# Main.net
KiCad netlist of a schematic drawn in Altium Designer
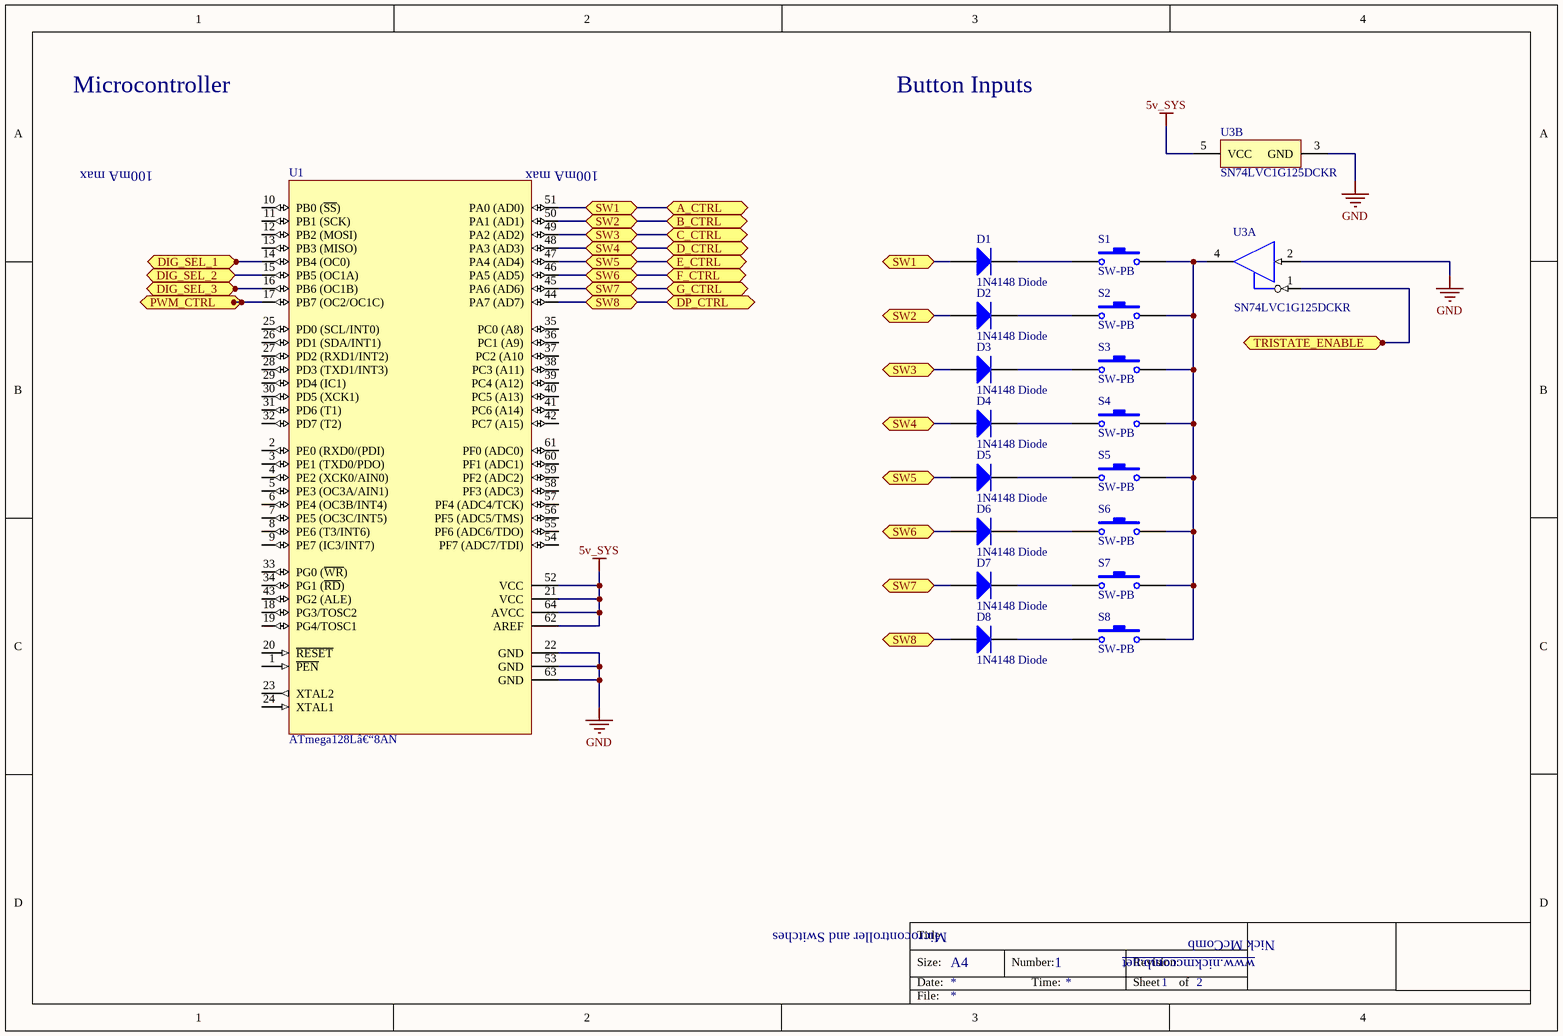
[diagram p0: Main.SchDoc]

(export (version "E")
  (design (tool "Eeschema 10.0.6"))
  (components
    (comp (ref "D1")
      (value "1N4148 Diode")
      (footprint "S01575 Diode")
      (description "Diode")
      (libsource (lib "lab2") (part "Diode"))
    )
    (comp (ref "D2")
      (value "1N4148 Diode")
      (footprint "S01575 Diode")
      (description "Diode")
      (libsource (lib "lab2") (part "Diode"))
    )
    (comp (ref "D3")
      (value "1N4148 Diode")
      (footprint "S01575 Diode")
      (description "Diode")
      (libsource (lib "lab2") (part "Diode"))
    )
    (comp (ref "D4")
      (value "1N4148 Diode")
      (footprint "S01575 Diode")
      (description "Diode")
      (libsource (lib "lab2") (part "Diode"))
    )
    (comp (ref "D5")
      (value "1N4148 Diode")
      (footprint "S01575 Diode")
      (description "Diode")
      (libsource (lib "lab2") (part "Diode"))
    )
    (comp (ref "D6")
      (value "1N4148 Diode")
      (footprint "S01575 Diode")
      (description "Diode")
      (libsource (lib "lab2") (part "Diode"))
    )
    (comp (ref "D7")
      (value "1N4148 Diode")
      (footprint "S01575 Diode")
      (description "Diode")
      (libsource (lib "lab2") (part "Diode"))
    )
    (comp (ref "D8")
      (value "1N4148 Diode")
      (footprint "S01575 Diode")
      (description "Diode")
      (libsource (lib "lab2") (part "Diode"))
    )
    (comp (ref "S1")
      (value "SW-PB")
      (footprint "SW-PB")
      (description "Switch")
      (libsource (lib "lab2") (part "SW-PB"))
    )
    (comp (ref "S2")
      (value "SW-PB")
      (footprint "SW-PB")
      (description "Switch")
      (libsource (lib "lab2") (part "SW-PB"))
    )
    (comp (ref "S3")
      (value "SW-PB")
      (footprint "SW-PB")
      (description "Switch")
      (libsource (lib "lab2") (part "SW-PB"))
    )
    (comp (ref "S4")
      (value "SW-PB")
      (footprint "SW-PB")
      (description "Switch")
      (libsource (lib "lab2") (part "SW-PB"))
    )
    (comp (ref "S5")
      (value "SW-PB")
      (footprint "SW-PB")
      (description "Switch")
      (libsource (lib "lab2") (part "SW-PB"))
    )
    (comp (ref "S6")
      (value "SW-PB")
      (footprint "SW-PB")
      (description "Switch")
      (libsource (lib "lab2") (part "SW-PB"))
    )
    (comp (ref "S7")
      (value "SW-PB")
      (footprint "SW-PB")
      (description "Switch")
      (libsource (lib "lab2") (part "SW-PB"))
    )
    (comp (ref "S8")
      (value "SW-PB")
      (footprint "SW-PB")
      (description "Switch")
      (libsource (lib "lab2") (part "SW-PB"))
    )
    (comp (ref "U1")
      (value "ATmega128Lâ€“8AN")
      (footprint "64A_M")
      (libsource (lib "Altium Content Vault") (part "MC-8B-AT64-SQ64"))
    )
    (comp (ref "U3")
      (value "SN74LVC1G125DCKR")
      (footprint "DCK0005A_M")
      (description "Single Bus Buffer Gate With 3-State Outputs, DCK0005A, LARGE T&R")
      (fields
        (field (name "GENERIC PART NUMBER") "SN74LVC1G125")
        (field (name "MANUFACTURER") "Texas Instruments")
      )
      (libsource (lib "") (part "TI-SN74AXXXX1X125-5_1"))
    )
  )
  (nets
    (net (code "1") (name "/A_CTRL") (class "Default")
      (node (ref "D1") (pin "3") (pinfunction "A_3") (pintype "passive"))
      (node (ref "U1") (pin "51") (pinfunction "PA0_(AD0)_51") (pintype "bidirectional"))
    )
    (net (code "2") (name "/B_CTRL") (class "Default")
      (node (ref "D2") (pin "3") (pinfunction "A_3") (pintype "passive"))
      (node (ref "U1") (pin "50") (pinfunction "PA1_(AD1)_50") (pintype "bidirectional"))
    )
    (net (code "3") (name "/C_CTRL") (class "Default")
      (node (ref "D3") (pin "3") (pinfunction "A_3") (pintype "passive"))
      (node (ref "U1") (pin "49") (pinfunction "PA2_(AD2)_49") (pintype "bidirectional"))
    )
    (net (code "4") (name "/DIG_SEL_1") (class "Default")
      (node (ref "U1") (pin "14") (pinfunction "PB4_(OC0)_14") (pintype "bidirectional"))
    )
    (net (code "5") (name "/DIG_SEL_2") (class "Default")
      (node (ref "U1") (pin "15") (pinfunction "PB5_(OC1A)_15") (pintype "bidirectional"))
    )
    (net (code "6") (name "/DIG_SEL_3") (class "Default")
      (node (ref "U1") (pin "16") (pinfunction "PB6_(OC1B)_16") (pintype "bidirectional"))
    )
    (net (code "7") (name "/DP_CTRL") (class "Default")
      (node (ref "D8") (pin "3") (pinfunction "A_3") (pintype "passive"))
      (node (ref "U1") (pin "44") (pinfunction "PA7_(AD7)_44") (pintype "bidirectional"))
    )
    (net (code "8") (name "/D_CTRL") (class "Default")
      (node (ref "D4") (pin "3") (pinfunction "A_3") (pintype "passive"))
      (node (ref "U1") (pin "48") (pinfunction "PA3_(AD3)_48") (pintype "bidirectional"))
    )
    (net (code "9") (name "/E_CTRL") (class "Default")
      (node (ref "D5") (pin "3") (pinfunction "A_3") (pintype "passive"))
      (node (ref "U1") (pin "47") (pinfunction "PA4_(AD4)_47") (pintype "bidirectional"))
    )
    (net (code "10") (name "/F_CTRL") (class "Default")
      (node (ref "D6") (pin "3") (pinfunction "A_3") (pintype "passive"))
      (node (ref "U1") (pin "46") (pinfunction "PA5_(AD5)_46") (pintype "bidirectional"))
    )
    (net (code "11") (name "/G_CTRL") (class "Default")
      (node (ref "D7") (pin "3") (pinfunction "A_3") (pintype "passive"))
      (node (ref "U1") (pin "45") (pinfunction "PA6_(AD6)_45") (pintype "bidirectional"))
    )
    (net (code "12") (name "/PWM_CTRL") (class "Default")
      (node (ref "U1") (pin "17") (pinfunction "PB7_(OC2/OC1C)_17") (pintype "bidirectional"))
    )
    (net (code "13") (name "/TRISTATE_ENABLE") (class "Default")
      (node (ref "U3") (pin "1") (pinfunction "~{OE}_1") (pintype "input"))
    )
    (net (code "14") (name "5v_SYS") (class "Default")
      (node (ref "U1") (pin "21") (pinfunction "VCC_21") (pintype "power_in"))
      (node (ref "U1") (pin "52") (pinfunction "VCC_52") (pintype "power_in"))
      (node (ref "U1") (pin "62") (pinfunction "AREF_62") (pintype "passive"))
      (node (ref "U1") (pin "64") (pinfunction "AVCC_64") (pintype "power_in"))
      (node (ref "U3") (pin "5") (pinfunction "VCC_5") (pintype "power_in"))
    )
    (net (code "15") (name "GND") (class "Default")
      (node (ref "U1") (pin "22") (pinfunction "GND_22") (pintype "power_in"))
      (node (ref "U1") (pin "53") (pinfunction "GND_53") (pintype "power_in"))
      (node (ref "U1") (pin "63") (pinfunction "GND_63") (pintype "power_in"))
      (node (ref "U3") (pin "2") (pinfunction "A_2") (pintype "input"))
      (node (ref "U3") (pin "3") (pinfunction "GND_3") (pintype "power_in"))
    )
    (net (code "16") (name "Net-(D1-K)") (class "Default")
      (node (ref "D1") (pin "1") (pinfunction "K_1") (pintype "passive"))
      (node (ref "S1") (pin "1") (pinfunction "1_1") (pintype "passive"))
    )
    (net (code "17") (name "Net-(D2-K)") (class "Default")
      (node (ref "D2") (pin "1") (pinfunction "K_1") (pintype "passive"))
      (node (ref "S2") (pin "1") (pinfunction "1_1") (pintype "passive"))
    )
    (net (code "18") (name "Net-(D3-K)") (class "Default")
      (node (ref "D3") (pin "1") (pinfunction "K_1") (pintype "passive"))
      (node (ref "S3") (pin "1") (pinfunction "1_1") (pintype "passive"))
    )
    (net (code "19") (name "Net-(D4-K)") (class "Default")
      (node (ref "D4") (pin "1") (pinfunction "K_1") (pintype "passive"))
      (node (ref "S4") (pin "1") (pinfunction "1_1") (pintype "passive"))
    )
    (net (code "20") (name "Net-(D5-K)") (class "Default")
      (node (ref "D5") (pin "1") (pinfunction "K_1") (pintype "passive"))
      (node (ref "S5") (pin "1") (pinfunction "1_1") (pintype "passive"))
    )
    (net (code "21") (name "Net-(D6-K)") (class "Default")
      (node (ref "D6") (pin "1") (pinfunction "K_1") (pintype "passive"))
      (node (ref "S6") (pin "1") (pinfunction "1_1") (pintype "passive"))
    )
    (net (code "22") (name "Net-(D7-K)") (class "Default")
      (node (ref "D7") (pin "1") (pinfunction "K_1") (pintype "passive"))
      (node (ref "S7") (pin "1") (pinfunction "1_1") (pintype "passive"))
    )
    (net (code "23") (name "Net-(D8-K)") (class "Default")
      (node (ref "D8") (pin "1") (pinfunction "K_1") (pintype "passive"))
      (node (ref "S8") (pin "1") (pinfunction "1_1") (pintype "passive"))
    )
    (net (code "24") (name "Net-(U3A-Y)") (class "Default")
      (node (ref "S1") (pin "2") (pinfunction "2_2") (pintype "passive"))
      (node (ref "S2") (pin "2") (pinfunction "2_2") (pintype "passive"))
      (node (ref "S3") (pin "2") (pinfunction "2_2") (pintype "passive"))
      (node (ref "S4") (pin "2") (pinfunction "2_2") (pintype "passive"))
      (node (ref "S5") (pin "2") (pinfunction "2_2") (pintype "passive"))
      (node (ref "S6") (pin "2") (pinfunction "2_2") (pintype "passive"))
      (node (ref "S7") (pin "2") (pinfunction "2_2") (pintype "passive"))
      (node (ref "S8") (pin "2") (pinfunction "2_2") (pintype "passive"))
      (node (ref "U3") (pin "4") (pinfunction "Y_4") (pintype "tri_state"))
    )
    (net (code "25") (name "unconnected-(U1-PB0_(~{SS})-Pad10)") (class "Default")
      (node (ref "U1") (pin "10") (pinfunction "PB0_(~{SS})_10") (pintype "bidirectional"))
    )
    (net (code "26") (name "unconnected-(U1-PB1_(SCK)-Pad11)") (class "Default")
      (node (ref "U1") (pin "11") (pinfunction "PB1_(SCK)_11") (pintype "bidirectional"))
    )
    (net (code "27") (name "unconnected-(U1-PB2_(MOSI)-Pad12)") (class "Default")
      (node (ref "U1") (pin "12") (pinfunction "PB2_(MOSI)_12") (pintype "bidirectional"))
    )
    (net (code "28") (name "unconnected-(U1-PB3_(MISO)-Pad13)") (class "Default")
      (node (ref "U1") (pin "13") (pinfunction "PB3_(MISO)_13") (pintype "bidirectional"))
    )
    (net (code "29") (name "unconnected-(U1-PC0_(A8)-Pad35)") (class "Default")
      (node (ref "U1") (pin "35") (pinfunction "PC0_(A8)_35") (pintype "bidirectional"))
    )
    (net (code "30") (name "unconnected-(U1-PC1_(A9)-Pad36)") (class "Default")
      (node (ref "U1") (pin "36") (pinfunction "PC1_(A9)_36") (pintype "bidirectional"))
    )
    (net (code "31") (name "unconnected-(U1-PC2_(A10-Pad37)") (class "Default")
      (node (ref "U1") (pin "37") (pinfunction "PC2_(A10_37") (pintype "bidirectional"))
    )
    (net (code "32") (name "unconnected-(U1-PC3_(A11)-Pad38)") (class "Default")
      (node (ref "U1") (pin "38") (pinfunction "PC3_(A11)_38") (pintype "bidirectional"))
    )
    (net (code "33") (name "unconnected-(U1-PC4_(A12)-Pad39)") (class "Default")
      (node (ref "U1") (pin "39") (pinfunction "PC4_(A12)_39") (pintype "bidirectional"))
    )
    (net (code "34") (name "unconnected-(U1-PC5_(A13)-Pad40)") (class "Default")
      (node (ref "U1") (pin "40") (pinfunction "PC5_(A13)_40") (pintype "bidirectional"))
    )
    (net (code "35") (name "unconnected-(U1-PC6_(A14)-Pad41)") (class "Default")
      (node (ref "U1") (pin "41") (pinfunction "PC6_(A14)_41") (pintype "bidirectional"))
    )
    (net (code "36") (name "unconnected-(U1-PC7_(A15)-Pad42)") (class "Default")
      (node (ref "U1") (pin "42") (pinfunction "PC7_(A15)_42") (pintype "bidirectional"))
    )
    (net (code "37") (name "unconnected-(U1-PD0_(SCL{slash}INT0)-Pad25)") (class "Default")
      (node (ref "U1") (pin "25") (pinfunction "PD0_(SCL/INT0)_25") (pintype "bidirectional"))
    )
    (net (code "38") (name "unconnected-(U1-PD1_(SDA{slash}INT1)-Pad26)") (class "Default")
      (node (ref "U1") (pin "26") (pinfunction "PD1_(SDA/INT1)_26") (pintype "bidirectional"))
    )
    (net (code "39") (name "unconnected-(U1-PD2_(RXD1{slash}INT2)-Pad27)") (class "Default")
      (node (ref "U1") (pin "27") (pinfunction "PD2_(RXD1/INT2)_27") (pintype "bidirectional"))
    )
    (net (code "40") (name "unconnected-(U1-PD3_(TXD1{slash}INT3)-Pad28)") (class "Default")
      (node (ref "U1") (pin "28") (pinfunction "PD3_(TXD1/INT3)_28") (pintype "bidirectional"))
    )
    (net (code "41") (name "unconnected-(U1-PD4_(IC1)-Pad29)") (class "Default")
      (node (ref "U1") (pin "29") (pinfunction "PD4_(IC1)_29") (pintype "bidirectional"))
    )
    (net (code "42") (name "unconnected-(U1-PD5_(XCK1)-Pad30)") (class "Default")
      (node (ref "U1") (pin "30") (pinfunction "PD5_(XCK1)_30") (pintype "bidirectional"))
    )
    (net (code "43") (name "unconnected-(U1-PD6_(T1)-Pad31)") (class "Default")
      (node (ref "U1") (pin "31") (pinfunction "PD6_(T1)_31") (pintype "bidirectional"))
    )
    (net (code "44") (name "unconnected-(U1-PD7_(T2)-Pad32)") (class "Default")
      (node (ref "U1") (pin "32") (pinfunction "PD7_(T2)_32") (pintype "bidirectional"))
    )
    (net (code "45") (name "unconnected-(U1-PE0_(RXD0{slash}(PDI)-Pad2)") (class "Default")
      (node (ref "U1") (pin "2") (pinfunction "PE0_(RXD0/(PDI)_2") (pintype "bidirectional"))
    )
    (net (code "46") (name "unconnected-(U1-PE1_(TXD0{slash}PDO)-Pad3)") (class "Default")
      (node (ref "U1") (pin "3") (pinfunction "PE1_(TXD0/PDO)_3") (pintype "bidirectional"))
    )
    (net (code "47") (name "unconnected-(U1-PE2_(XCK0{slash}AIN0)-Pad4)") (class "Default")
      (node (ref "U1") (pin "4") (pinfunction "PE2_(XCK0/AIN0)_4") (pintype "bidirectional"))
    )
    (net (code "48") (name "unconnected-(U1-PE3_(OC3A{slash}AIN1)-Pad5)") (class "Default")
      (node (ref "U1") (pin "5") (pinfunction "PE3_(OC3A/AIN1)_5") (pintype "bidirectional"))
    )
    (net (code "49") (name "unconnected-(U1-PE4_(OC3B{slash}INT4)-Pad6)") (class "Default")
      (node (ref "U1") (pin "6") (pinfunction "PE4_(OC3B/INT4)_6") (pintype "bidirectional"))
    )
    (net (code "50") (name "unconnected-(U1-PE5_(OC3C{slash}INT5)-Pad7)") (class "Default")
      (node (ref "U1") (pin "7") (pinfunction "PE5_(OC3C/INT5)_7") (pintype "bidirectional"))
    )
    (net (code "51") (name "unconnected-(U1-PE6_(T3{slash}INT6)-Pad8)") (class "Default")
      (node (ref "U1") (pin "8") (pinfunction "PE6_(T3/INT6)_8") (pintype "bidirectional"))
    )
    (net (code "52") (name "unconnected-(U1-PE7_(IC3{slash}INT7)-Pad9)") (class "Default")
      (node (ref "U1") (pin "9") (pinfunction "PE7_(IC3/INT7)_9") (pintype "bidirectional"))
    )
    (net (code "53") (name "unconnected-(U1-PF0_(ADC0)-Pad61)") (class "Default")
      (node (ref "U1") (pin "61") (pinfunction "PF0_(ADC0)_61") (pintype "bidirectional"))
    )
    (net (code "54") (name "unconnected-(U1-PF1_(ADC1)-Pad60)") (class "Default")
      (node (ref "U1") (pin "60") (pinfunction "PF1_(ADC1)_60") (pintype "bidirectional"))
    )
    (net (code "55") (name "unconnected-(U1-PF2_(ADC2)-Pad59)") (class "Default")
      (node (ref "U1") (pin "59") (pinfunction "PF2_(ADC2)_59") (pintype "bidirectional"))
    )
    (net (code "56") (name "unconnected-(U1-PF3_(ADC3)-Pad58)") (class "Default")
      (node (ref "U1") (pin "58") (pinfunction "PF3_(ADC3)_58") (pintype "bidirectional"))
    )
    (net (code "57") (name "unconnected-(U1-PF4_(ADC4{slash}TCK)-Pad57)") (class "Default")
      (node (ref "U1") (pin "57") (pinfunction "PF4_(ADC4/TCK)_57") (pintype "bidirectional"))
    )
    (net (code "58") (name "unconnected-(U1-PF5_(ADC5{slash}TMS)-Pad56)") (class "Default")
      (node (ref "U1") (pin "56") (pinfunction "PF5_(ADC5/TMS)_56") (pintype "bidirectional"))
    )
    (net (code "59") (name "unconnected-(U1-PF6_(ADC6{slash}TDO)-Pad55)") (class "Default")
      (node (ref "U1") (pin "55") (pinfunction "PF6_(ADC6/TDO)_55") (pintype "bidirectional"))
    )
    (net (code "60") (name "unconnected-(U1-PF7_(ADC7{slash}TDI)-Pad54)") (class "Default")
      (node (ref "U1") (pin "54") (pinfunction "PF7_(ADC7/TDI)_54") (pintype "bidirectional"))
    )
    (net (code "61") (name "unconnected-(U1-PG0_(~{WR})-Pad33)") (class "Default")
      (node (ref "U1") (pin "33") (pinfunction "PG0_(~{WR})_33") (pintype "bidirectional"))
    )
    (net (code "62") (name "unconnected-(U1-PG1_(~{RD})-Pad34)") (class "Default")
      (node (ref "U1") (pin "34") (pinfunction "PG1_(~{RD})_34") (pintype "bidirectional"))
    )
    (net (code "63") (name "unconnected-(U1-PG2_(ALE)-Pad43)") (class "Default")
      (node (ref "U1") (pin "43") (pinfunction "PG2_(ALE)_43") (pintype "bidirectional"))
    )
    (net (code "64") (name "unconnected-(U1-PG3{slash}TOSC2-Pad18)") (class "Default")
      (node (ref "U1") (pin "18") (pinfunction "PG3/TOSC2_18") (pintype "bidirectional"))
    )
    (net (code "65") (name "unconnected-(U1-PG4{slash}TOSC1-Pad19)") (class "Default")
      (node (ref "U1") (pin "19") (pinfunction "PG4/TOSC1_19") (pintype "bidirectional"))
    )
    (net (code "66") (name "unconnected-(U1-XTAL1-Pad24)") (class "Default")
      (node (ref "U1") (pin "24") (pinfunction "XTAL1_24") (pintype "input"))
    )
    (net (code "67") (name "unconnected-(U1-XTAL2-Pad23)") (class "Default")
      (node (ref "U1") (pin "23") (pinfunction "XTAL2_23") (pintype "output"))
    )
    (net (code "68") (name "unconnected-(U1-~{PEN}-Pad1)") (class "Default")
      (node (ref "U1") (pin "1") (pinfunction "~{PEN}_1") (pintype "input"))
    )
    (net (code "69") (name "unconnected-(U1-~{RESET}-Pad20)") (class "Default")
      (node (ref "U1") (pin "20") (pinfunction "~{RESET}_20") (pintype "input"))
    )
  )
)
